# Fri3d_2020_Time_Blaster_02.net
KiCad netlist of a schematic drawn in Altium Designer
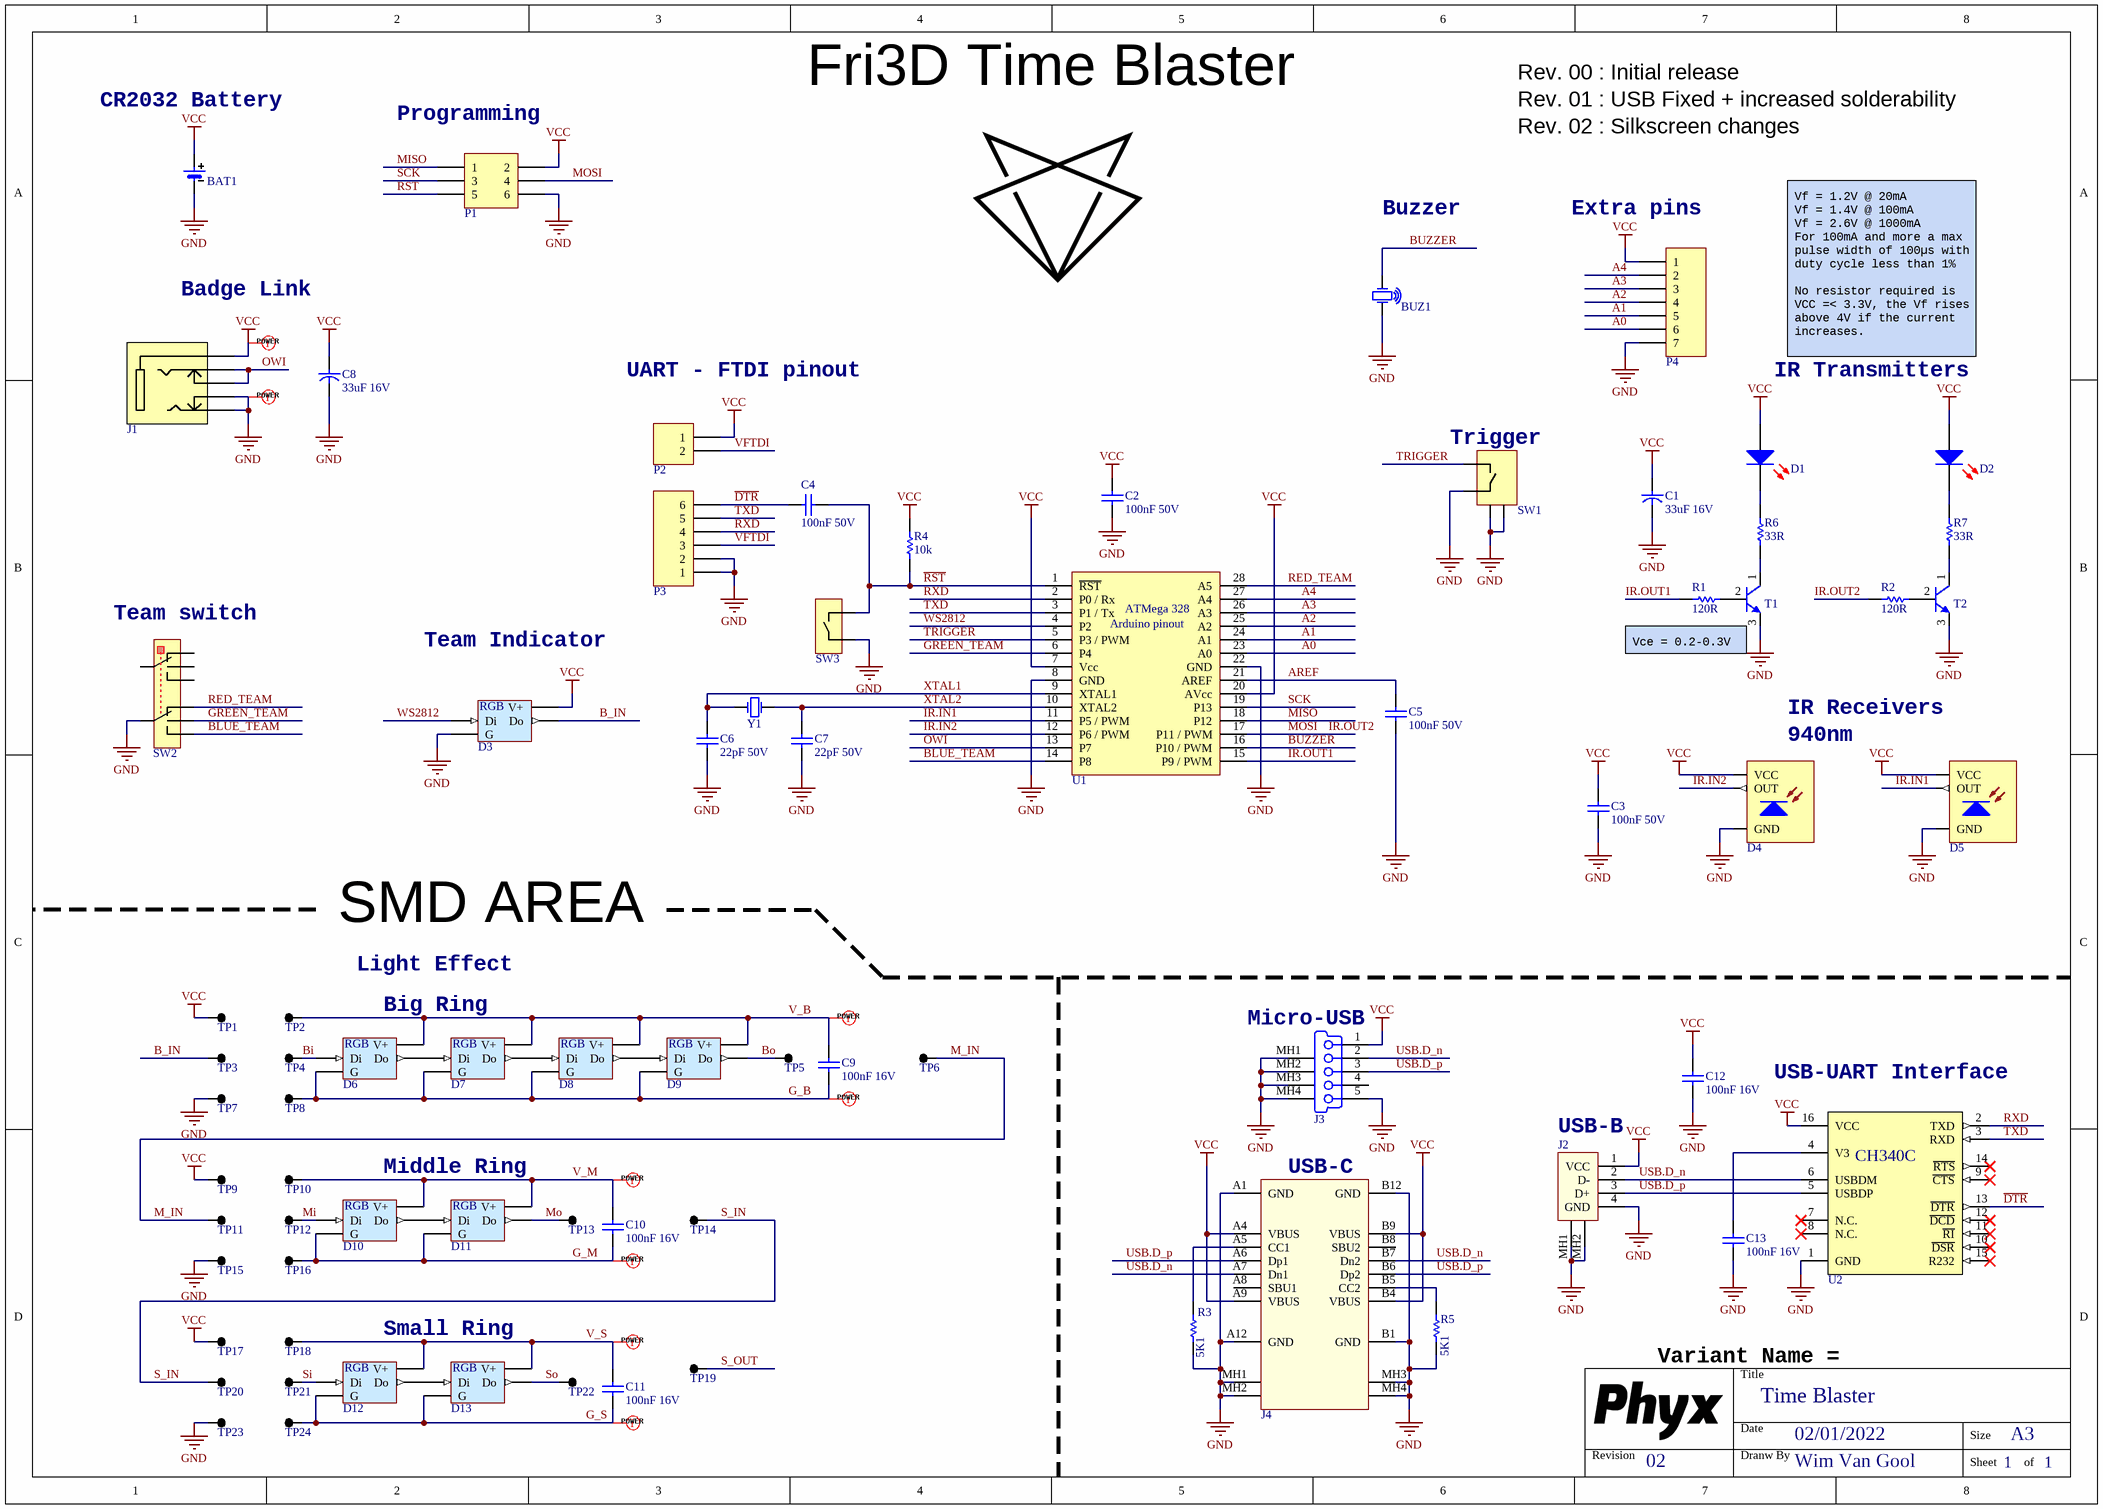
[diagram p0: Fri3d_2020_Time_Blaster_02.SchDoc]

(export (version "E")
  (design (tool "Eeschema 10.0.6"))
  (components
    (comp (ref "BAT1")
      (value "CR2032 Battery Holder")
      (footprint "BAT_CR2032_China")
      (description "=Description")
      (libsource (lib "Phyx_Components") (part "BAT_2"))
    )
    (comp (ref "BUZ1")
      (value "14x14x7mm Piezo Buzzer Transducer 80dB")
      (footprint "CUI_CEP-1162")
      (description "Crystal Oscillator")
      (libsource (lib "Phyx_Components") (part "Buzzer"))
    )
    (comp (ref "C1")
      (value "33uF 16V")
      (footprint "C_4x7_1.5mm")
      (description "Capacitor electrolyt")
      (fields (field (name "Comment") "CAP_POL"))
      (libsource (lib "Phyx_Components") (part "CAP_POL"))
    )
    (comp (ref "C2")
      (value "100nF 50V")
      (footprint "C_5.08mm")
      (description "Capacitor Ceramic")
      (fields (field (name "Comment") "CAP_CERAMIC"))
      (libsource (lib "Phyx_Components") (part "CAP_CERAMIC"))
    )
    (comp (ref "C3")
      (value "100nF 50V")
      (footprint "C_5.08mm")
      (description "Capacitor Ceramic")
      (fields (field (name "Comment") "CAP_CERAMIC"))
      (libsource (lib "Phyx_Components") (part "CAP_CERAMIC"))
    )
    (comp (ref "C4")
      (value "100nF 50V")
      (footprint "C_5.08mm")
      (description "Capacitor Ceramic")
      (fields (field (name "Comment") "CAP_CERAMIC"))
      (libsource (lib "Phyx_Components") (part "CAP_CERAMIC"))
    )
    (comp (ref "C5")
      (value "100nF 50V")
      (footprint "C_5.08mm")
      (description "Capacitor Ceramic")
      (fields (field (name "Comment") "CAP_CERAMIC"))
      (libsource (lib "Phyx_Components") (part "CAP_CERAMIC"))
    )
    (comp (ref "C6")
      (value "22pF 50V")
      (footprint "C_5.08mm")
      (description "Capacitor Ceramic")
      (fields (field (name "Comment") "CAP_CERAMIC"))
      (libsource (lib "Phyx_Components") (part "CAP_CERAMIC"))
    )
    (comp (ref "C7")
      (value "22pF 50V")
      (footprint "C_5.08mm")
      (description "Capacitor Ceramic")
      (fields (field (name "Comment") "CAP_CERAMIC"))
      (libsource (lib "Phyx_Components") (part "CAP_CERAMIC"))
    )
    (comp (ref "C8")
      (value "33uF 16V")
      (footprint "C_4x7_1.5mm")
      (description "Capacitor electrolyt")
      (fields (field (name "Comment") "CAP_POL"))
      (libsource (lib "Phyx_Components") (part "CAP_POL"))
    )
    (comp (ref "C9")
      (value "100nF 16V")
      (footprint "C0805_N")
      (description "Capacitor Ceramic")
      (fields (field (name "Comment") "CAP_CERAMIC"))
      (libsource (lib "Phyx_Components") (part "CAP_CERAMIC"))
    )
    (comp (ref "C10")
      (value "100nF 16V")
      (footprint "C0805_N")
      (description "Capacitor Ceramic")
      (fields (field (name "Comment") "CAP_CERAMIC"))
      (libsource (lib "Phyx_Components") (part "CAP_CERAMIC"))
    )
    (comp (ref "C11")
      (value "100nF 16V")
      (footprint "C0805_N")
      (description "Capacitor Ceramic")
      (fields (field (name "Comment") "CAP_CERAMIC"))
      (libsource (lib "Phyx_Components") (part "CAP_CERAMIC"))
    )
    (comp (ref "C12")
      (value "100nF 16V")
      (footprint "C0805_N")
      (description "Capacitor Ceramic")
      (fields (field (name "Comment") "CAP_CERAMIC"))
      (libsource (lib "Phyx_Components") (part "CAP_CERAMIC"))
    )
    (comp (ref "C13")
      (value "100nF 16V")
      (footprint "C0805_N")
      (description "Capacitor Ceramic")
      (fields (field (name "Comment") "CAP_CERAMIC"))
      (libsource (lib "Phyx_Components") (part "CAP_CERAMIC"))
    )
    (comp (ref "D1")
      (value "5mm IR LED, 940nm, 100mA, 1.35V, 25Deg")
      (footprint "LED_5MM_RD")
      (description "=Description")
      (libsource (lib "Phyx_Components") (part "LED_RED"))
    )
    (comp (ref "D2")
      (value "5mm IR LED, 940nm, 100mA, 1.35V, 25Deg")
      (footprint "LED_5MM_RD")
      (description "=Description")
      (libsource (lib "Phyx_Components") (part "LED_RED"))
    )
    (comp (ref "D3")
      (value "WS2812 based digital RGB LED 5mm")
      (footprint "LED_5mm_RGB")
      (description "=Description")
      (libsource (lib "Phyx_Components") (part "LED_RGB_WS2812B_5mm"))
    )
    (comp (ref "D4")
      (value "IRM-3638N3F14 Infrared Receiver 38 kHz 45° 2.7-5.5V")
      (footprint "VIS_TSOP381x_BENT")
      (description "=Description")
      (libsource (lib "Phyx_Components") (part "PHO_IR_TSOP381x"))
    )
    (comp (ref "D5")
      (value "IRM-3638N3F14 Infrared Receiver 38 kHz 45° 2.7-5.5V")
      (footprint "VIS_TSOP381x_BENT")
      (description "=Description")
      (libsource (lib "Phyx_Components") (part "PHO_IR_TSOP381x"))
    )
    (comp (ref "D6")
      (value "WS2812 based digital RGB LED 5050 Black package")
      (footprint "LED_5050_WS2812B_BLACK")
      (description "=Description")
      (libsource (lib "Phyx_Components") (part "LED_RGB_WS2812B_5050"))
    )
    (comp (ref "D7")
      (value "WS2812 based digital RGB LED 5050 Black package")
      (footprint "LED_5050_WS2812B_BLACK")
      (description "=Description")
      (libsource (lib "Phyx_Components") (part "LED_RGB_WS2812B_5050"))
    )
    (comp (ref "D8")
      (value "WS2812 based digital RGB LED 5050 Black package")
      (footprint "LED_5050_WS2812B_BLACK")
      (description "=Description")
      (libsource (lib "Phyx_Components") (part "LED_RGB_WS2812B_5050"))
    )
    (comp (ref "D9")
      (value "WS2812 based digital RGB LED 5050 Black package")
      (footprint "LED_5050_WS2812B_BLACK")
      (description "=Description")
      (libsource (lib "Phyx_Components") (part "LED_RGB_WS2812B_5050"))
    )
    (comp (ref "D10")
      (value "WS2812 based digital RGB LED 5050 Black package")
      (footprint "LED_5050_WS2812B_BLACK")
      (description "=Description")
      (libsource (lib "Phyx_Components") (part "LED_RGB_WS2812B_5050"))
    )
    (comp (ref "D11")
      (value "WS2812 based digital RGB LED 5050 Black package")
      (footprint "LED_5050_WS2812B_BLACK")
      (description "=Description")
      (libsource (lib "Phyx_Components") (part "LED_RGB_WS2812B_5050"))
    )
    (comp (ref "D12")
      (value "WS2812 based digital RGB LED 5050 Black package")
      (footprint "LED_5050_WS2812B_BLACK")
      (description "=Description")
      (libsource (lib "Phyx_Components") (part "LED_RGB_WS2812B_5050"))
    )
    (comp (ref "D13")
      (value "WS2812 based digital RGB LED 5050 Black package")
      (footprint "LED_5050_WS2812B_BLACK")
      (description "=Description")
      (libsource (lib "Phyx_Components") (part "LED_RGB_WS2812B_5050"))
    )
    (comp (ref "J1")
      (value "3.5mm jack, dual switch, black, 3 contacts")
      (footprint "CUI_SJ1-3525NG")
      (description "=Description")
      (libsource (lib "Phyx_Components") (part "CUI_SJ1-3525NG"))
    )
    (comp (ref "J2")
      (value "Vertical USB B 61400416121")
      (footprint "WE_61400416121")
      (libsource (lib "Phyx_Components") (part "USB_A"))
    )
    (comp (ref "J3")
      (value "XKB U254-051T-4BH81-S2S Micro USB")
      (footprint "XKB_U254-051T-4BH81-S2S")
      (libsource (lib "Phyx_Components") (part "USB_OTG_Mini-B"))
    )
    (comp (ref "J4")
      (value "USB 2.0 C Reversible Receptacle Horizontal")
      (footprint "HRO_TYPE-C-31-M-12")
      (libsource (lib "Phyx_Components") (part "USB_C_16_4"))
    )
    (comp (ref "P1")
      (value "Boxed Header 3X2")
      (footprint "B_HDR2X3")
      (libsource (lib "Phyx_Components") (part "Header 3X2"))
    )
    (comp (ref "P2")
      (value "Easy to solder connection")
      (footprint "SOLDER_SW_V_1MM")
      (libsource (lib "Phyx_Components") (part "Header 2"))
    )
    (comp (ref "P3")
      (value "Header 6")
      (footprint "HDR1X6")
      (libsource (lib "Phyx_Components") (part "Header 6"))
    )
    (comp (ref "P4")
      (value "Header 7")
      (footprint "HDR1X7")
      (libsource (lib "Phyx_Components") (part "Header 7"))
    )
    (comp (ref "R1")
      (value "120R")
      (footprint "RES_10mm")
      (fields (field (name "Comment") "RESISTOR"))
      (libsource (lib "Phyx_Components") (part "RESISTOR"))
    )
    (comp (ref "R2")
      (value "120R")
      (footprint "RES_10mm")
      (fields (field (name "Comment") "RESISTOR"))
      (libsource (lib "Phyx_Components") (part "RESISTOR"))
    )
    (comp (ref "R3")
      (value "5K1")
      (footprint "R0805_N")
      (fields (field (name "Comment") "RESISTOR"))
      (libsource (lib "Phyx_Components") (part "RESISTOR"))
    )
    (comp (ref "R4")
      (value "10k")
      (footprint "RES_10mm")
      (fields (field (name "Comment") "RESISTOR"))
      (libsource (lib "Phyx_Components") (part "RESISTOR"))
    )
    (comp (ref "R5")
      (value "5K1")
      (footprint "R0805_N")
      (fields (field (name "Comment") "RESISTOR"))
      (libsource (lib "Phyx_Components") (part "RESISTOR"))
    )
    (comp (ref "R6")
      (value "33R")
      (footprint "RES_10mm")
      (fields (field (name "Comment") "RESISTOR"))
      (libsource (lib "Phyx_Components") (part "RESISTOR"))
    )
    (comp (ref "R7")
      (value "33R")
      (footprint "RES_10mm")
      (fields (field (name "Comment") "RESISTOR"))
      (libsource (lib "Phyx_Components") (part "RESISTOR"))
    )
    (comp (ref "SW1")
      (value "Tact switch, RA, 3,85mm")
      (footprint "TACTSW_RA_385")
      (libsource (lib "Phyx_Components") (part "SW_TACT_RA"))
    )
    (comp (ref "SW2")
      (value "Slide switch dual pole triple throw")
      (footprint "CK_JS203011CQN")
      (libsource (lib "Phyx_Components") (part "SW_2P3T"))
    )
    (comp (ref "SW3")
      (value "Default TH TACT")
      (footprint "TACTSW")
      (libsource (lib "Phyx_Components") (part "SW_TACT"))
    )
    (comp (ref "T1")
      (value "0.2A 40V 100hfe NPN Transistor")
      (footprint "TO-92A _EASY")
      (libsource (lib "Phyx_Components") (part "NPN_EBC"))
    )
    (comp (ref "T2")
      (value "0.2A 40V 100hfe NPN Transistor")
      (footprint "TO-92A _EASY")
      (libsource (lib "Phyx_Components") (part "NPN_EBC"))
    )
    (comp (ref "TP1")
      (value "TEST_PAD")
      (footprint "TP_2x3mm")
      (libsource (lib "Phyx_Components") (part "TEST_PAD"))
    )
    (comp (ref "TP2")
      (value "TEST_PAD")
      (footprint "TP_2x3mm")
      (libsource (lib "Phyx_Components") (part "TEST_PAD"))
    )
    (comp (ref "TP3")
      (value "TEST_PAD")
      (footprint "TP_2x3mm")
      (libsource (lib "Phyx_Components") (part "TEST_PAD"))
    )
    (comp (ref "TP4")
      (value "TEST_PAD")
      (footprint "TP_2x3mm")
      (libsource (lib "Phyx_Components") (part "TEST_PAD"))
    )
    (comp (ref "TP5")
      (value "TEST_PAD")
      (footprint "TP_2x3mm")
      (libsource (lib "Phyx_Components") (part "TEST_PAD"))
    )
    (comp (ref "TP6")
      (value "TEST_PAD")
      (footprint "TP_2x3mm")
      (libsource (lib "Phyx_Components") (part "TEST_PAD"))
    )
    (comp (ref "TP7")
      (value "TEST_PAD")
      (footprint "TP_2x3mm")
      (libsource (lib "Phyx_Components") (part "TEST_PAD"))
    )
    (comp (ref "TP8")
      (value "TEST_PAD")
      (footprint "TP_2x3mm")
      (libsource (lib "Phyx_Components") (part "TEST_PAD"))
    )
    (comp (ref "TP9")
      (value "TEST_PAD")
      (footprint "TP_2x3mm")
      (libsource (lib "Phyx_Components") (part "TEST_PAD"))
    )
    (comp (ref "TP10")
      (value "TEST_PAD")
      (footprint "TP_2x3mm")
      (libsource (lib "Phyx_Components") (part "TEST_PAD"))
    )
    (comp (ref "TP11")
      (value "TEST_PAD")
      (footprint "TP_2x3mm")
      (libsource (lib "Phyx_Components") (part "TEST_PAD"))
    )
    (comp (ref "TP12")
      (value "TEST_PAD")
      (footprint "TP_2x3mm")
      (libsource (lib "Phyx_Components") (part "TEST_PAD"))
    )
    (comp (ref "TP13")
      (value "TEST_PAD")
      (footprint "TP_2x3mm")
      (libsource (lib "Phyx_Components") (part "TEST_PAD"))
    )
    (comp (ref "TP14")
      (value "TEST_PAD")
      (footprint "TP_2x3mm")
      (libsource (lib "Phyx_Components") (part "TEST_PAD"))
    )
    (comp (ref "TP15")
      (value "TEST_PAD")
      (footprint "TP_2x3mm")
      (libsource (lib "Phyx_Components") (part "TEST_PAD"))
    )
    (comp (ref "TP16")
      (value "TEST_PAD")
      (footprint "TP_2x3mm")
      (libsource (lib "Phyx_Components") (part "TEST_PAD"))
    )
    (comp (ref "TP17")
      (value "TEST_PAD")
      (footprint "TP_2x3mm")
      (libsource (lib "Phyx_Components") (part "TEST_PAD"))
    )
    (comp (ref "TP18")
      (value "TEST_PAD")
      (footprint "TP_2x3mm")
      (libsource (lib "Phyx_Components") (part "TEST_PAD"))
    )
    (comp (ref "TP19")
      (value "TEST_PAD")
      (footprint "TP_2x3mm")
      (libsource (lib "Phyx_Components") (part "TEST_PAD"))
    )
    (comp (ref "TP20")
      (value "TEST_PAD")
      (footprint "TP_2x3mm")
      (libsource (lib "Phyx_Components") (part "TEST_PAD"))
    )
    (comp (ref "TP21")
      (value "TEST_PAD")
      (footprint "TP_2x3mm")
      (libsource (lib "Phyx_Components") (part "TEST_PAD"))
    )
    (comp (ref "TP22")
      (value "TEST_PAD")
      (footprint "TP_2x3mm")
      (libsource (lib "Phyx_Components") (part "TEST_PAD"))
    )
    (comp (ref "TP23")
      (value "TEST_PAD")
      (footprint "TP_2x3mm")
      (libsource (lib "Phyx_Components") (part "TEST_PAD"))
    )
    (comp (ref "TP24")
      (value "TEST_PAD")
      (footprint "TP_2x3mm")
      (libsource (lib "Phyx_Components") (part "TEST_PAD"))
    )
    (comp (ref "U1")
      (value "8-bit MCU")
      (footprint "DIP_N_28")
      (libsource (lib "Phyx_Components") (part "ATMega328_DIP28"))
    )
    (comp (ref "U2")
      (value "USB to full UART with internal crystal")
      (footprint "SOIC_N_16")
      (description "=Description")
      (libsource (lib "Phyx_Components") (part "CH340C"))
    )
    (comp (ref "Y1")
      (value "16MHz 18pF HC49US")
      (footprint "HC49US")
      (description "Crystal Oscillator")
      (libsource (lib "Phyx_Components") (part "XTAL"))
    )
  )
  (nets
    (net (code "1") (name "/A0") (class "Default")
      (node (ref "P4") (pin "6") (pinfunction "6_6") (pintype "passive"))
      (node (ref "U1") (pin "23") (pinfunction "A0_23") (pintype "passive"))
    )
    (net (code "2") (name "/A1") (class "Default")
      (node (ref "P4") (pin "5") (pinfunction "5_5") (pintype "passive"))
      (node (ref "U1") (pin "24") (pinfunction "A1_24") (pintype "passive"))
    )
    (net (code "3") (name "/A2") (class "Default")
      (node (ref "P4") (pin "4") (pinfunction "4_4") (pintype "passive"))
      (node (ref "U1") (pin "25") (pinfunction "A2_25") (pintype "passive"))
    )
    (net (code "4") (name "/A3") (class "Default")
      (node (ref "P4") (pin "3") (pinfunction "3_3") (pintype "passive"))
      (node (ref "U1") (pin "26") (pinfunction "A3_26") (pintype "passive"))
    )
    (net (code "5") (name "/A4") (class "Default")
      (node (ref "P4") (pin "2") (pinfunction "2_2") (pintype "passive"))
      (node (ref "U1") (pin "27") (pinfunction "A4_27") (pintype "passive"))
    )
    (net (code "6") (name "/AREF") (class "Default")
      (node (ref "C5") (pin "1") (pinfunction "1_1") (pintype "passive"))
      (node (ref "U1") (pin "21") (pinfunction "AREF_21") (pintype "passive"))
    )
    (net (code "7") (name "/BLUE_TEAM") (class "Default")
      (node (ref "SW2") (pin "8") (pinfunction "8_8") (pintype "passive"))
      (node (ref "U1") (pin "14") (pinfunction "P8_14") (pintype "passive"))
    )
    (net (code "8") (name "/BUZZER") (class "Default")
      (node (ref "BUZ1") (pin "2") (pinfunction "OSC2_2") (pintype "passive"))
      (node (ref "U1") (pin "16") (pinfunction "P10_/_PWM_16") (pintype "passive"))
    )
    (net (code "9") (name "/B_IN") (class "Default")
      (node (ref "D3") (pin "1") (pinfunction "Do_1") (pintype "output"))
      (node (ref "TP3") (pin "1") (pinfunction "1_1") (pintype "passive"))
    )
    (net (code "10") (name "/Bi") (class "Default")
      (node (ref "D6") (pin "4") (pinfunction "Di_4") (pintype "input"))
      (node (ref "TP4") (pin "1") (pinfunction "1_1") (pintype "passive"))
    )
    (net (code "11") (name "/Bo") (class "Default")
      (node (ref "D9") (pin "2") (pinfunction "Do_2") (pintype "output"))
      (node (ref "TP5") (pin "1") (pinfunction "1_1") (pintype "passive"))
    )
    (net (code "12") (name "/GREEN_TEAM") (class "Default")
      (node (ref "SW2") (pin "6") (pinfunction "6_6") (pintype "passive"))
      (node (ref "U1") (pin "6") (pinfunction "P4_6") (pintype "passive"))
    )
    (net (code "13") (name "/G_B") (class "Default")
      (node (ref "C9") (pin "2") (pinfunction "2_2") (pintype "passive"))
      (node (ref "D6") (pin "3") (pinfunction "G_3") (pintype "power_in"))
      (node (ref "D7") (pin "3") (pinfunction "G_3") (pintype "power_in"))
      (node (ref "D8") (pin "3") (pinfunction "G_3") (pintype "power_in"))
      (node (ref "D9") (pin "3") (pinfunction "G_3") (pintype "power_in"))
      (node (ref "TP8") (pin "1") (pinfunction "1_1") (pintype "passive"))
    )
    (net (code "14") (name "/G_M") (class "Default")
      (node (ref "C10") (pin "2") (pinfunction "2_2") (pintype "passive"))
      (node (ref "D10") (pin "3") (pinfunction "G_3") (pintype "power_in"))
      (node (ref "D11") (pin "3") (pinfunction "G_3") (pintype "power_in"))
      (node (ref "TP16") (pin "1") (pinfunction "1_1") (pintype "passive"))
    )
    (net (code "15") (name "/G_S") (class "Default")
      (node (ref "C11") (pin "2") (pinfunction "2_2") (pintype "passive"))
      (node (ref "D12") (pin "3") (pinfunction "G_3") (pintype "power_in"))
      (node (ref "D13") (pin "3") (pinfunction "G_3") (pintype "power_in"))
      (node (ref "TP24") (pin "1") (pinfunction "1_1") (pintype "passive"))
    )
    (net (code "16") (name "/IR.IN1") (class "Default")
      (node (ref "D5") (pin "1") (pinfunction "OUT_1") (pintype "output"))
      (node (ref "U1") (pin "11") (pinfunction "P5_/_PWM_11") (pintype "passive"))
    )
    (net (code "17") (name "/IR.IN2") (class "Default")
      (node (ref "D4") (pin "1") (pinfunction "OUT_1") (pintype "output"))
      (node (ref "U1") (pin "12") (pinfunction "P6_/_PWM_12") (pintype "passive"))
    )
    (net (code "18") (name "/IR.OUT1") (class "Default")
      (node (ref "R1") (pin "2") (pinfunction "2_2") (pintype "passive"))
      (node (ref "U1") (pin "15") (pinfunction "P9_/_PWM_15") (pintype "passive"))
    )
    (net (code "19") (name "/IR.OUT2") (class "Default")
      (node (ref "P1") (pin "4") (pinfunction "4_4") (pintype "passive"))
      (node (ref "R2") (pin "2") (pinfunction "2_2") (pintype "passive"))
      (node (ref "U1") (pin "17") (pinfunction "P11_/_PWM_17") (pintype "passive"))
    )
    (net (code "20") (name "/MISO") (class "Default")
      (node (ref "P1") (pin "1") (pinfunction "1_1") (pintype "passive"))
      (node (ref "U1") (pin "18") (pinfunction "P12_18") (pintype "passive"))
    )
    (net (code "21") (name "/M_IN") (class "Default")
      (node (ref "TP11") (pin "1") (pinfunction "1_1") (pintype "passive"))
      (node (ref "TP6") (pin "1") (pinfunction "1_1") (pintype "passive"))
    )
    (net (code "22") (name "/Mi") (class "Default")
      (node (ref "D10") (pin "4") (pinfunction "Di_4") (pintype "input"))
      (node (ref "TP12") (pin "1") (pinfunction "1_1") (pintype "passive"))
    )
    (net (code "23") (name "/Mo") (class "Default")
      (node (ref "D11") (pin "2") (pinfunction "Do_2") (pintype "output"))
      (node (ref "TP13") (pin "1") (pinfunction "1_1") (pintype "passive"))
    )
    (net (code "24") (name "/OWI") (class "Default")
      (node (ref "J1") (pin "3") (pinfunction "Ring_3") (pintype "passive"))
      (node (ref "J1") (pin "5") (pinfunction "5_5") (pintype "passive"))
      (node (ref "U1") (pin "13") (pinfunction "P7_13") (pintype "passive"))
    )
    (net (code "25") (name "/RED_TEAM") (class "Default")
      (node (ref "SW2") (pin "5") (pinfunction "5_5") (pintype "passive"))
      (node (ref "U1") (pin "28") (pinfunction "A5_28") (pintype "passive"))
    )
    (net (code "26") (name "/RXD") (class "Default")
      (node (ref "P3") (pin "4") (pinfunction "4_4") (pintype "passive"))
      (node (ref "U1") (pin "2") (pinfunction "P0_/_Rx_2") (pintype "passive"))
      (node (ref "U2") (pin "2") (pinfunction "TXD_2") (pintype "output"))
    )
    (net (code "27") (name "/SCK") (class "Default")
      (node (ref "P1") (pin "3") (pinfunction "3_3") (pintype "passive"))
      (node (ref "U1") (pin "19") (pinfunction "P13_19") (pintype "passive"))
    )
    (net (code "28") (name "/S_IN") (class "Default")
      (node (ref "TP14") (pin "1") (pinfunction "1_1") (pintype "passive"))
      (node (ref "TP20") (pin "1") (pinfunction "1_1") (pintype "passive"))
    )
    (net (code "29") (name "/S_OUT") (class "Default")
      (node (ref "TP19") (pin "1") (pinfunction "1_1") (pintype "passive"))
    )
    (net (code "30") (name "/Si") (class "Default")
      (node (ref "D12") (pin "4") (pinfunction "Di_4") (pintype "input"))
      (node (ref "TP21") (pin "1") (pinfunction "1_1") (pintype "passive"))
    )
    (net (code "31") (name "/So") (class "Default")
      (node (ref "D13") (pin "2") (pinfunction "Do_2") (pintype "output"))
      (node (ref "TP22") (pin "1") (pinfunction "1_1") (pintype "passive"))
    )
    (net (code "32") (name "/TRIGGER") (class "Default")
      (node (ref "SW1") (pin "1") (pinfunction "1_1") (pintype "passive"))
      (node (ref "U1") (pin "5") (pinfunction "P3_/_PWM_5") (pintype "passive"))
    )
    (net (code "33") (name "/TXD") (class "Default")
      (node (ref "P3") (pin "5") (pinfunction "5_5") (pintype "passive"))
      (node (ref "U1") (pin "3") (pinfunction "P1_/_Tx_3") (pintype "passive"))
      (node (ref "U2") (pin "3") (pinfunction "RXD_3") (pintype "input"))
    )
    (net (code "34") (name "/USB.D_n") (class "Default")
      (node (ref "J2") (pin "2") (pinfunction "D-_2") (pintype "passive"))
      (node (ref "J3") (pin "2") (pinfunction "D-_2") (pintype "passive"))
      (node (ref "J4") (pin "A7") (pinfunction "Dn1_A7") (pintype "passive"))
      (node (ref "J4") (pin "B7") (pinfunction "Dn2_B7") (pintype "passive"))
      (node (ref "U2") (pin "6") (pinfunction "USBDM_6") (pintype "passive"))
    )
    (net (code "35") (name "/USB.D_p") (class "Default")
      (node (ref "J2") (pin "3") (pinfunction "D+_3") (pintype "passive"))
      (node (ref "J3") (pin "3") (pinfunction "D+_3") (pintype "passive"))
      (node (ref "J4") (pin "A6") (pinfunction "Dp1_A6") (pintype "passive"))
      (node (ref "J4") (pin "B6") (pinfunction "Dp2_B6") (pintype "passive"))
      (node (ref "U2") (pin "5") (pinfunction "USBDP_5") (pintype "passive"))
    )
    (net (code "36") (name "/VFTDI") (class "Default")
      (node (ref "P2") (pin "2") (pinfunction "2_2") (pintype "passive"))
      (node (ref "P3") (pin "3") (pinfunction "3_3") (pintype "passive"))
    )
    (net (code "37") (name "/V_B") (class "Default")
      (node (ref "C9") (pin "1") (pinfunction "1_1") (pintype "passive"))
      (node (ref "D6") (pin "1") (pinfunction "V+_1") (pintype "power_in"))
      (node (ref "D7") (pin "1") (pinfunction "V+_1") (pintype "power_in"))
      (node (ref "D8") (pin "1") (pinfunction "V+_1") (pintype "power_in"))
      (node (ref "D9") (pin "1") (pinfunction "V+_1") (pintype "power_in"))
      (node (ref "TP2") (pin "1") (pinfunction "1_1") (pintype "passive"))
    )
    (net (code "38") (name "/V_M") (class "Default")
      (node (ref "C10") (pin "1") (pinfunction "1_1") (pintype "passive"))
      (node (ref "D10") (pin "1") (pinfunction "V+_1") (pintype "power_in"))
      (node (ref "D11") (pin "1") (pinfunction "V+_1") (pintype "power_in"))
      (node (ref "TP10") (pin "1") (pinfunction "1_1") (pintype "passive"))
    )
    (net (code "39") (name "/V_S") (class "Default")
      (node (ref "C11") (pin "1") (pinfunction "1_1") (pintype "passive"))
      (node (ref "D12") (pin "1") (pinfunction "V+_1") (pintype "power_in"))
      (node (ref "D13") (pin "1") (pinfunction "V+_1") (pintype "power_in"))
      (node (ref "TP18") (pin "1") (pinfunction "1_1") (pintype "passive"))
    )
    (net (code "40") (name "/WS2812") (class "Default")
      (node (ref "D3") (pin "4") (pinfunction "Di_4") (pintype "input"))
      (node (ref "U1") (pin "4") (pinfunction "P2_4") (pintype "passive"))
    )
    (net (code "41") (name "/XTAL1") (class "Default")
      (node (ref "C6") (pin "1") (pinfunction "1_1") (pintype "passive"))
      (node (ref "U1") (pin "9") (pinfunction "XTAL1_9") (pintype "passive"))
      (node (ref "Y1") (pin "1") (pinfunction "OSC1_1") (pintype "passive"))
    )
    (net (code "42") (name "/XTAL2") (class "Default")
      (node (ref "C7") (pin "1") (pinfunction "1_1") (pintype "passive"))
      (node (ref "U1") (pin "10") (pinfunction "XTAL2_10") (pintype "passive"))
      (node (ref "Y1") (pin "2") (pinfunction "OSC2_2") (pintype "passive"))
    )
    (net (code "43") (name "/~{DTR}") (class "Default")
      (node (ref "C4") (pin "2") (pinfunction "2_2") (pintype "passive"))
      (node (ref "P3") (pin "6") (pinfunction "6_6") (pintype "passive"))
      (node (ref "U2") (pin "13") (pinfunction "~{DTR}_13") (pintype "output"))
    )
    (net (code "44") (name "/~{RST}") (class "Default")
      (node (ref "C4") (pin "1") (pinfunction "1_1") (pintype "passive"))
      (node (ref "P1") (pin "5") (pinfunction "5_5") (pintype "passive"))
      (node (ref "R4") (pin "2") (pinfunction "2_2") (pintype "passive"))
      (node (ref "SW3") (pin "1") (pinfunction "1_1") (pintype "passive"))
      (node (ref "U1") (pin "1") (pinfunction "~{RST}_1") (pintype "passive"))
    )
    (net (code "45") (name "GND") (class "Default")
      (node (ref "BAT1") (pin "2") (pinfunction "2_2") (pintype "passive"))
      (node (ref "BUZ1") (pin "1") (pinfunction "OSC1_1") (pintype "passive"))
      (node (ref "C1") (pin "2") (pinfunction "2_2") (pintype "passive"))
      (node (ref "C12") (pin "2") (pinfunction "2_2") (pintype "passive"))
      (node (ref "C13") (pin "2") (pinfunction "2_2") (pintype "passive"))
      (node (ref "C2") (pin "2") (pinfunction "2_2") (pintype "passive"))
      (node (ref "C3") (pin "2") (pinfunction "2_2") (pintype "passive"))
      (node (ref "C5") (pin "2") (pinfunction "2_2") (pintype "passive"))
      (node (ref "C6") (pin "2") (pinfunction "2_2") (pintype "passive"))
      (node (ref "C7") (pin "2") (pinfunction "2_2") (pintype "passive"))
      (node (ref "C8") (pin "2") (pinfunction "2_2") (pintype "passive"))
      (node (ref "D3") (pin "3") (pinfunction "G_3") (pintype "power_in"))
      (node (ref "D4") (pin "2") (pinfunction "GND_2") (pintype "power_in"))
      (node (ref "D5") (pin "2") (pinfunction "GND_2") (pintype "power_in"))
      (node (ref "J1") (pin "2") (pinfunction "Tip_2") (pintype "passive"))
      (node (ref "J1") (pin "4") (pinfunction "4_4") (pintype "passive"))
      (node (ref "J2") (pin "4") (pinfunction "GND_4") (pintype "passive"))
      (node (ref "J2") (pin "MH1") (pinfunction "Tab_MH1") (pintype "passive"))
      (node (ref "J2") (pin "MH2") (pinfunction "Tab_MH2") (pintype "passive"))
      (node (ref "J3") (pin "5") (pinfunction "GND_5") (pintype "passive"))
      (node (ref "J3") (pin "MH1") (pinfunction "Tab_MH1") (pintype "passive"))
      (node (ref "J3") (pin "MH2") (pinfunction "Tab_MH2") (pintype "passive"))
      (node (ref "J3") (pin "MH3") (pinfunction "Tab_MH3") (pintype "passive"))
      (node (ref "J3") (pin "MH4") (pinfunction "Tab_MH4") (pintype "passive"))
      (node (ref "J4") (pin "A1") (pinfunction "GND_A1") (pintype "passive"))
      (node (ref "J4") (pin "A12") (pinfunction "GND_A12") (pintype "passive"))
      (node (ref "J4") (pin "B1") (pinfunction "GND_B1") (pintype "passive"))
      (node (ref "J4") (pin "B12") (pinfunction "GND_B12") (pintype "passive"))
      (node (ref "J4") (pin "MH1") (pinfunction "Tab_MH1") (pintype "passive"))
      (node (ref "J4") (pin "MH2") (pinfunction "Tab_MH2") (pintype "passive"))
      (node (ref "J4") (pin "MH3") (pinfunction "Tab_MH3") (pintype "passive"))
      (node (ref "J4") (pin "MH4") (pinfunction "Tab_MH4") (pintype "passive"))
      (node (ref "P1") (pin "6") (pinfunction "6_6") (pintype "passive"))
      (node (ref "P3") (pin "1") (pinfunction "1_1") (pintype "passive"))
      (node (ref "P3") (pin "2") (pinfunction "2_2") (pintype "passive"))
      (node (ref "P4") (pin "7") (pinfunction "7_7") (pintype "passive"))
      (node (ref "R3") (pin "2") (pinfunction "2_2") (pintype "passive"))
      (node (ref "R5") (pin "2") (pinfunction "2_2") (pintype "passive"))
      (node (ref "SW1") (pin "2") (pinfunction "2_2") (pintype "passive"))
      (node (ref "SW1") (pin "MH1") (pinfunction "MH1_MH1") (pintype "passive"))
      (node (ref "SW1") (pin "MH2") (pinfunction "MH2_MH2") (pintype "passive"))
      (node (ref "SW2") (pin "7") (pinfunction "7_7") (pintype "passive"))
      (node (ref "SW3") (pin "2") (pinfunction "2_2") (pintype "passive"))
      (node (ref "T1") (pin "3") (pinfunction "E_3") (pintype "passive"))
      (node (ref "T2") (pin "3") (pinfunction "E_3") (pintype "passive"))
      (node (ref "TP15") (pin "1") (pinfunction "1_1") (pintype "passive"))
      (node (ref "TP23") (pin "1") (pinfunction "1_1") (pintype "passive"))
      (node (ref "TP7") (pin "1") (pinfunction "1_1") (pintype "passive"))
      (node (ref "U1") (pin "22") (pinfunction "GND_22") (pintype "power_in"))
      (node (ref "U1") (pin "8") (pinfunction "GND_8") (pintype "power_in"))
      (node (ref "U2") (pin "1") (pinfunction "GND_1") (pintype "power_in"))
    )
    (net (code "46") (name "Net-(D1-K)") (class "Default")
      (node (ref "D1") (pin "2") (pinfunction "K_2") (pintype "passive"))
      (node (ref "R6") (pin "1") (pinfunction "1_1") (pintype "passive"))
    )
    (net (code "47") (name "Net-(D2-K)") (class "Default")
      (node (ref "D2") (pin "2") (pinfunction "K_2") (pintype "passive"))
      (node (ref "R7") (pin "1") (pinfunction "1_1") (pintype "passive"))
    )
    (net (code "48") (name "Net-(D6-Do)") (class "Default")
      (node (ref "D6") (pin "2") (pinfunction "Do_2") (pintype "output"))
      (node (ref "D7") (pin "4") (pinfunction "Di_4") (pintype "input"))
    )
    (net (code "49") (name "Net-(D7-Do)") (class "Default")
      (node (ref "D7") (pin "2") (pinfunction "Do_2") (pintype "output"))
      (node (ref "D8") (pin "4") (pinfunction "Di_4") (pintype "input"))
    )
    (net (code "50") (name "Net-(D8-Do)") (class "Default")
      (node (ref "D8") (pin "2") (pinfunction "Do_2") (pintype "output"))
      (node (ref "D9") (pin "4") (pinfunction "Di_4") (pintype "input"))
    )
    (net (code "51") (name "Net-(D10-Do)") (class "Default")
      (node (ref "D10") (pin "2") (pinfunction "Do_2") (pintype "output"))
      (node (ref "D11") (pin "4") (pinfunction "Di_4") (pintype "input"))
    )
    (net (code "52") (name "Net-(D12-Do)") (class "Default")
      (node (ref "D12") (pin "2") (pinfunction "Do_2") (pintype "output"))
      (node (ref "D13") (pin "4") (pinfunction "Di_4") (pintype "input"))
    )
    (net (code "53") (name "Net-(J4-CC1)") (class "Default")
      (node (ref "J4") (pin "A5") (pinfunction "CC1_A5") (pintype "passive"))
      (node (ref "R3") (pin "1") (pinfunction "1_1") (pintype "passive"))
    )
    (net (code "54") (name "Net-(J4-CC2)") (class "Default")
      (node (ref "J4") (pin "B5") (pinfunction "CC2_B5") (pintype "passive"))
      (node (ref "R5") (pin "1") (pinfunction "1_1") (pintype "passive"))
    )
    (net (code "55") (name "Net-(T1-B)") (class "Default")
      (node (ref "R1") (pin "1") (pinfunction "1_1") (pintype "passive"))
      (node (ref "T1") (pin "2") (pinfunction "B_2") (pintype "passive"))
    )
    (net (code "56") (name "Net-(T1-C)") (class "Default")
      (node (ref "R6") (pin "2") (pinfunction "2_2") (pintype "passive"))
      (node (ref "T1") (pin "1") (pinfunction "C_1") (pintype "passive"))
    )
    (net (code "57") (name "Net-(T2-B)") (class "Default")
      (node (ref "R2") (pin "1") (pinfunction "1_1") (pintype "passive"))
      (node (ref "T2") (pin "2") (pinfunction "B_2") (pintype "passive"))
    )
    (net (code "58") (name "Net-(T2-C)") (class "Default")
      (node (ref "R7") (pin "2") (pinfunction "2_2") (pintype "passive"))
      (node (ref "T2") (pin "1") (pinfunction "C_1") (pintype "passive"))
    )
    (net (code "59") (name "Net-(U2-V3)") (class "Default")
      (node (ref "C13") (pin "1") (pinfunction "1_1") (pintype "passive"))
      (node (ref "U2") (pin "4") (pinfunction "V3_4") (pintype "power_in"))
    )
    (net (code "60") (name "VCC") (class "Default")
      (node (ref "BAT1") (pin "1") (pinfunction "1_1") (pintype "passive"))
      (node (ref "C1") (pin "1") (pinfunction "1_1") (pintype "passive"))
      (node (ref "C12") (pin "1") (pinfunction "1_1") (pintype "passive"))
      (node (ref "C2") (pin "1") (pinfunction "1_1") (pintype "passive"))
      (node (ref "C3") (pin "1") (pinfunction "1_1") (pintype "passive"))
      (node (ref "C8") (pin "1") (pinfunction "1_1") (pintype "passive"))
      (node (ref "D1") (pin "1") (pinfunction "A_1") (pintype "passive"))
      (node (ref "D2") (pin "1") (pinfunction "A_1") (pintype "passive"))
      (node (ref "D3") (pin "2") (pinfunction "V+_2") (pintype "power_in"))
      (node (ref "D4") (pin "3") (pinfunction "VCC_3") (pintype "power_in"))
      (node (ref "D5") (pin "3") (pinfunction "VCC_3") (pintype "power_in"))
      (node (ref "J1") (pin "1") (pinfunction "Sleeve_1") (pintype "passive"))
      (node (ref "J2") (pin "1") (pinfunction "VCC_1") (pintype "passive"))
      (node (ref "J3") (pin "1") (pinfunction "V_BUS_(5V)_1") (pintype "passive"))
      (node (ref "J4") (pin "A4") (pinfunction "VBUS_A4") (pintype "passive"))
      (node (ref "J4") (pin "A9") (pinfunction "VBUS_A9") (pintype "passive"))
      (node (ref "J4") (pin "B4") (pinfunction "VBUS_B4") (pintype "passive"))
      (node (ref "J4") (pin "B9") (pinfunction "VBUS_B9") (pintype "passive"))
      (node (ref "P1") (pin "2") (pinfunction "2_2") (pintype "passive"))
      (node (ref "P2") (pin "1") (pinfunction "1_1") (pintype "passive"))
      (node (ref "P4") (pin "1") (pinfunction "1_1") (pintype "passive"))
      (node (ref "R4") (pin "1") (pinfunction "1_1") (pintype "passive"))
      (node (ref "TP1") (pin "1") (pinfunction "1_1") (pintype "passive"))
      (node (ref "TP17") (pin "1") (pinfunction "1_1") (pintype "passive"))
      (node (ref "TP9") (pin "1") (pinfunction "1_1") (pintype "passive"))
      (node (ref "U1") (pin "20") (pinfunction "AVcc_20") (pintype "power_in"))
      (node (ref "U1") (pin "7") (pinfunction "Vcc_7") (pintype "power_in"))
      (node (ref "U2") (pin "16") (pinfunction "VCC_16") (pintype "power_in"))
    )
    (net (code "61") (name "unconnected-(J3-NC-Pad4)") (class "Default")
      (node (ref "J3") (pin "4") (pinfunction "NC_4") (pintype "passive"))
    )
    (net (code "62") (name "unconnected-(J4-SBU1-PadA8)") (class "Default")
      (node (ref "J4") (pin "A8") (pinfunction "SBU1_A8") (pintype "passive"))
    )
    (net (code "63") (name "unconnected-(J4-SBU2-PadB8)") (class "Default")
      (node (ref "J4") (pin "B8") (pinfunction "SBU2_B8") (pintype "passive"))
    )
    (net (code "64") (name "unconnected-(SW2-Pad1)") (class "Default")
      (node (ref "SW2") (pin "1") (pinfunction "1_1") (pintype "passive"))
    )
    (net (code "65") (name "unconnected-(SW2-Pad2)") (class "Default")
      (node (ref "SW2") (pin "2") (pinfunction "2_2") (pintype "passive"))
    )
    (net (code "66") (name "unconnected-(SW2-Pad3)") (class "Default")
      (node (ref "SW2") (pin "3") (pinfunction "3_3") (pintype "passive"))
    )
    (net (code "67") (name "unconnected-(SW2-Pad4)") (class "Default")
      (node (ref "SW2") (pin "4") (pinfunction "4_4") (pintype "passive"))
    )
    (net (code "68") (name "unconnected-(U2-N.C.-Pad7)") (class "Default")
      (node (ref "U2") (pin "7") (pinfunction "N.C._7") (pintype "passive+no_connect"))
    )
    (net (code "69") (name "unconnected-(U2-N.C.-Pad8)") (class "Default")
      (node (ref "U2") (pin "8") (pinfunction "N.C._8") (pintype "passive+no_connect"))
    )
    (net (code "70") (name "unconnected-(U2-R232-Pad15)") (class "Default")
      (node (ref "U2") (pin "15") (pinfunction "R232_15") (pintype "input+no_connect"))
    )
    (net (code "71") (name "unconnected-(U2-~{CTS}-Pad9)") (class "Default")
      (node (ref "U2") (pin "9") (pinfunction "~{CTS}_9") (pintype "input+no_connect"))
    )
    (net (code "72") (name "unconnected-(U2-~{DCD}-Pad12)") (class "Default")
      (node (ref "U2") (pin "12") (pinfunction "~{DCD}_12") (pintype "input+no_connect"))
    )
    (net (code "73") (name "unconnected-(U2-~{DSR}-Pad10)") (class "Default")
      (node (ref "U2") (pin "10") (pinfunction "~{DSR}_10") (pintype "input+no_connect"))
    )
    (net (code "74") (name "unconnected-(U2-~{RI}-Pad11)") (class "Default")
      (node (ref "U2") (pin "11") (pinfunction "~{RI}_11") (pintype "input+no_connect"))
    )
    (net (code "75") (name "unconnected-(U2-~{RTS}-Pad14)") (class "Default")
      (node (ref "U2") (pin "14") (pinfunction "~{RTS}_14") (pintype "output+no_connect"))
    )
  )
)
